# battleswitch_v1.net
KiCad netlist of a schematic drawn in EAGLE
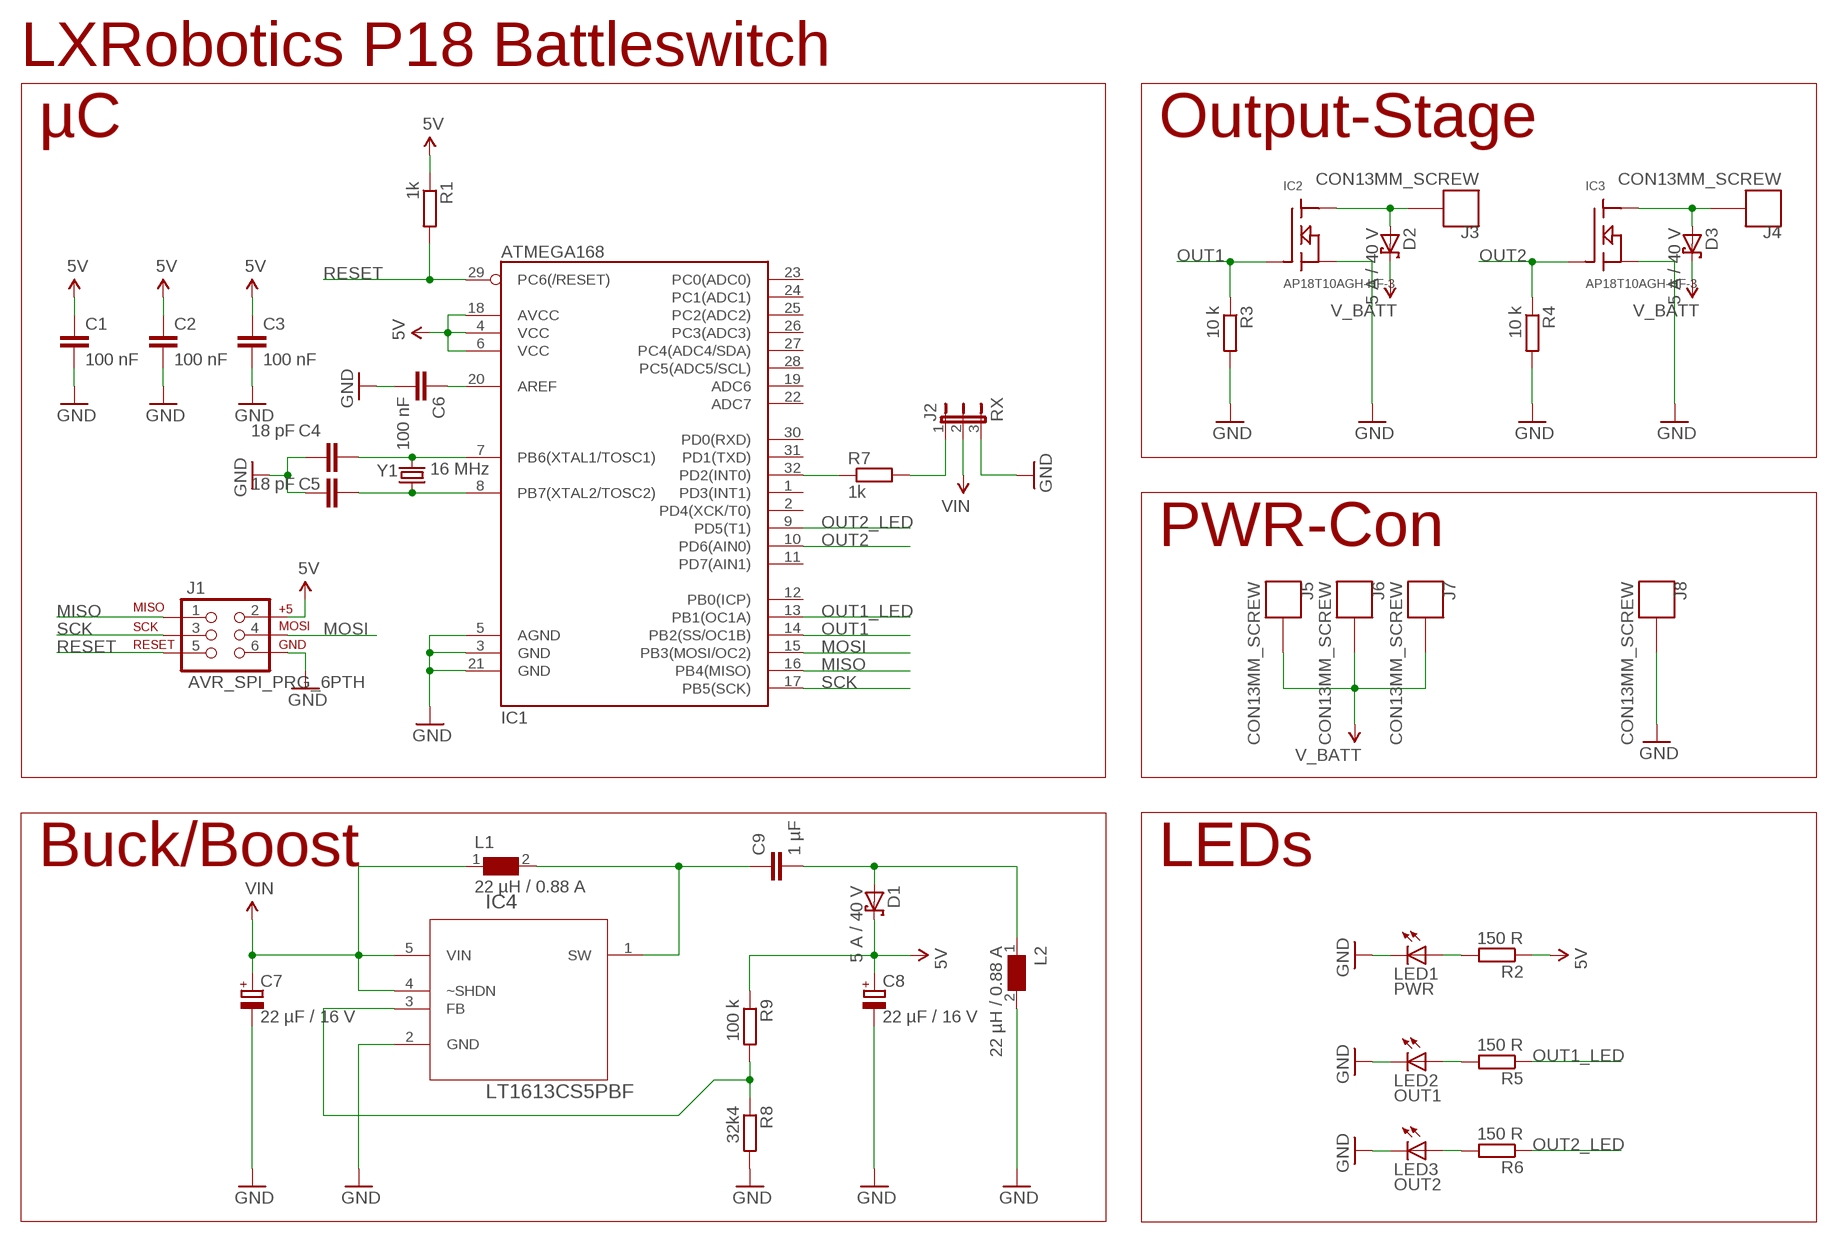
[diagram p0: schematic, sheet 1]

(export (version "E")
  (design (tool "Eeschema 10.0.6"))
  (components
    (comp (ref "C1")
      (value "100 nF")
      (footprint "eagle-import:C0805")
      (libsource (lib "eagle-import") (part "C-EUC0805"))
    )
    (comp (ref "C2")
      (value "100 nF")
      (footprint "eagle-import:C0805")
      (libsource (lib "eagle-import") (part "C-EUC0805"))
    )
    (comp (ref "C3")
      (value "100 nF")
      (footprint "eagle-import:C0805")
      (libsource (lib "eagle-import") (part "C-EUC0805"))
    )
    (comp (ref "C4")
      (value "18 pF")
      (footprint "eagle-import:C0805")
      (libsource (lib "eagle-import") (part "C-EUC0805"))
    )
    (comp (ref "C5")
      (value "18 pF")
      (footprint "eagle-import:C0805")
      (libsource (lib "eagle-import") (part "C-EUC0805"))
    )
    (comp (ref "C6")
      (value "100 nF")
      (footprint "eagle-import:C0805")
      (libsource (lib "eagle-import") (part "C-EUC0805"))
    )
    (comp (ref "C7")
      (value "22 µF / 16 V")
      (footprint "eagle-import:PANASONIC_C")
      (libsource (lib "eagle-import") (part "CPOL-EUC"))
    )
    (comp (ref "C8")
      (value "22 µF / 16 V")
      (footprint "eagle-import:PANASONIC_C")
      (libsource (lib "eagle-import") (part "CPOL-EUC"))
    )
    (comp (ref "C9")
      (value "1 µF")
      (footprint "eagle-import:C0805")
      (libsource (lib "eagle-import") (part "C-EUC0805"))
    )
    (comp (ref "D1")
      (value "5 A / 40 V")
      (footprint "eagle-import:SMC")
      (libsource (lib "eagle-import") (part "SCHOTTKY-DIODESMC"))
    )
    (comp (ref "D2")
      (value "5 A / 40 V")
      (footprint "eagle-import:SMC")
      (libsource (lib "eagle-import") (part "SCHOTTKY-DIODESMC"))
    )
    (comp (ref "D3")
      (value "5 A / 40 V")
      (footprint "eagle-import:SMC")
      (libsource (lib "eagle-import") (part "SCHOTTKY-DIODESMC"))
    )
    (comp (ref "IC1")
      (value "ATMEGA168")
      (footprint "eagle-import:TQFP32-08")
      (libsource (lib "eagle-import") (part "ATMEGA168"))
    )
    (comp (ref "IC2")
      (value "AP18T10AGH-HF-3")
      (footprint "eagle-import:TO252")
      (libsource (lib "eagle-import") (part "AP18T10AGH-HF-3"))
    )
    (comp (ref "IC3")
      (value "AP18T10AGH-HF-3")
      (footprint "eagle-import:TO252")
      (libsource (lib "eagle-import") (part "AP18T10AGH-HF-3"))
    )
    (comp (ref "IC4")
      (value "LT1613CS5PBF")
      (footprint "eagle-import:SOT95P280X145-5N")
      (fields (field (name "MPN") "LT1613CS5#PBF"))
      (libsource (lib "eagle-import") (part "LT1613CS5PBF"))
    )
    (comp (ref "J1")
      (value "AVR_SPI_PRG_6PTH")
      (footprint "eagle-import:2X3")
      (libsource (lib "eagle-import") (part "AVR_SPI_PRG_6PTH"))
    )
    (comp (ref "J2")
      (value "RX")
      (footprint "eagle-import:JP2")
      (libsource (lib "eagle-import") (part "JP2E"))
    )
    (comp (ref "J3")
      (value "CON13MM_SCREW")
      (footprint "eagle-import:CON1_3MM_SCREW")
      (libsource (lib "eagle-import") (part "CON13MM_SCREW"))
    )
    (comp (ref "J4")
      (value "CON13MM_SCREW")
      (footprint "eagle-import:CON1_3MM_SCREW")
      (libsource (lib "eagle-import") (part "CON13MM_SCREW"))
    )
    (comp (ref "J5")
      (value "CON13MM_SCREW")
      (footprint "eagle-import:CON1_3MM_SCREW")
      (libsource (lib "eagle-import") (part "CON13MM_SCREW"))
    )
    (comp (ref "J6")
      (value "CON13MM_SCREW")
      (footprint "eagle-import:CON1_3MM_SCREW")
      (libsource (lib "eagle-import") (part "CON13MM_SCREW"))
    )
    (comp (ref "J7")
      (value "CON13MM_SCREW")
      (footprint "eagle-import:CON1_3MM_SCREW")
      (libsource (lib "eagle-import") (part "CON13MM_SCREW"))
    )
    (comp (ref "J8")
      (value "CON13MM_SCREW")
      (footprint "eagle-import:CON1_3MM_SCREW")
      (libsource (lib "eagle-import") (part "CON13MM_SCREW"))
    )
    (comp (ref "L1")
      (value "22 µH / 0.88 A")
      (footprint "eagle-import:WE-TPC_4818_4828")
      (fields (field (name "MPN") "744042220 "))
      (libsource (lib "eagle-import") (part "WE-TPC_4818/4828-744042220"))
    )
    (comp (ref "L2")
      (value "22 µH / 0.88 A")
      (footprint "eagle-import:WE-TPC_4818_4828")
      (fields (field (name "MPN") "744042220 "))
      (libsource (lib "eagle-import") (part "WE-TPC_4818/4828-744042220"))
    )
    (comp (ref "LED1")
      (value "PWR")
      (footprint "eagle-import:CHIP-LED0805")
      (libsource (lib "eagle-import") (part "LEDCHIP-LED0805"))
    )
    (comp (ref "LED2")
      (value "OUT1")
      (footprint "eagle-import:CHIP-LED0805")
      (libsource (lib "eagle-import") (part "LEDCHIP-LED0805"))
    )
    (comp (ref "LED3")
      (value "OUT2")
      (footprint "eagle-import:CHIP-LED0805")
      (libsource (lib "eagle-import") (part "LEDCHIP-LED0805"))
    )
    (comp (ref "R1")
      (value "1k")
      (footprint "eagle-import:R0805")
      (libsource (lib "eagle-import") (part "R-EU_R0805"))
    )
    (comp (ref "R2")
      (value "150 R")
      (footprint "eagle-import:R0805")
      (libsource (lib "eagle-import") (part "R-EU_R0805"))
    )
    (comp (ref "R3")
      (value "10 k")
      (footprint "eagle-import:R0805")
      (libsource (lib "eagle-import") (part "R-EU_R0805"))
    )
    (comp (ref "R4")
      (value "10 k")
      (footprint "eagle-import:R0805")
      (libsource (lib "eagle-import") (part "R-EU_R0805"))
    )
    (comp (ref "R5")
      (value "150 R")
      (footprint "eagle-import:R0805")
      (libsource (lib "eagle-import") (part "R-EU_R0805"))
    )
    (comp (ref "R6")
      (value "150 R")
      (footprint "eagle-import:R0805")
      (libsource (lib "eagle-import") (part "R-EU_R0805"))
    )
    (comp (ref "R7")
      (value "1k")
      (footprint "eagle-import:R0805")
      (libsource (lib "eagle-import") (part "R-EU_R0805"))
    )
    (comp (ref "R8")
      (value "32k4")
      (footprint "eagle-import:R0805")
      (libsource (lib "eagle-import") (part "R-EU_R0805"))
    )
    (comp (ref "R9")
      (value "100 k")
      (footprint "eagle-import:R0805")
      (libsource (lib "eagle-import") (part "R-EU_R0805"))
    )
    (comp (ref "Y1")
      (value "16 MHz")
      (footprint "eagle-import:HC49US")
      (libsource (lib "eagle-import") (part "CRYSTALHC49US"))
    )
  )
  (nets
    (net (code "1") (name "/MISO") (class "Default")
      (node (ref "IC1") (pin "16") (pinfunction "PB4(MISO)_16") (pintype "bidirectional"))
      (node (ref "J1") (pin "1") (pinfunction "1_1") (pintype "passive"))
    )
    (net (code "2") (name "/MOSI") (class "Default")
      (node (ref "IC1") (pin "15") (pinfunction "PB3(MOSI/OC2)_15") (pintype "bidirectional"))
      (node (ref "J1") (pin "4") (pinfunction "4_4") (pintype "passive"))
    )
    (net (code "3") (name "/OUT1") (class "Default")
      (node (ref "IC1") (pin "14") (pinfunction "PB2(SS/OC1B)_14") (pintype "bidirectional"))
      (node (ref "IC2") (pin "G") (pinfunction "G_G") (pintype "bidirectional"))
      (node (ref "R3") (pin "1") (pinfunction "1_1") (pintype "passive"))
    )
    (net (code "4") (name "/OUT1_LED") (class "Default")
      (node (ref "IC1") (pin "13") (pinfunction "PB1(OC1A)_13") (pintype "bidirectional"))
      (node (ref "R5") (pin "1") (pinfunction "1_1") (pintype "passive"))
    )
    (net (code "5") (name "/OUT2") (class "Default")
      (node (ref "IC1") (pin "10") (pinfunction "PD6(AIN0)_10") (pintype "bidirectional"))
      (node (ref "IC3") (pin "G") (pinfunction "G_G") (pintype "bidirectional"))
      (node (ref "R4") (pin "1") (pinfunction "1_1") (pintype "passive"))
    )
    (net (code "6") (name "/OUT2_LED") (class "Default")
      (node (ref "IC1") (pin "9") (pinfunction "PD5(T1)_9") (pintype "bidirectional"))
      (node (ref "R6") (pin "1") (pinfunction "1_1") (pintype "passive"))
    )
    (net (code "7") (name "/RESET") (class "Default")
      (node (ref "IC1") (pin "29") (pinfunction "PC6(/RESET)_29") (pintype "bidirectional"))
      (node (ref "J1") (pin "5") (pinfunction "5_5") (pintype "passive"))
      (node (ref "R1") (pin "2") (pinfunction "2_2") (pintype "passive"))
    )
    (net (code "8") (name "/SCK") (class "Default")
      (node (ref "IC1") (pin "17") (pinfunction "PB5(SCK)_17") (pintype "bidirectional"))
      (node (ref "J1") (pin "3") (pinfunction "3_3") (pintype "passive"))
    )
    (net (code "9") (name "5V") (class "Default")
      (node (ref "C1") (pin "1") (pinfunction "1_1") (pintype "passive"))
      (node (ref "C2") (pin "1") (pinfunction "1_1") (pintype "passive"))
      (node (ref "C3") (pin "1") (pinfunction "1_1") (pintype "passive"))
      (node (ref "C8") (pin "+") (pinfunction "+_+") (pintype "passive"))
      (node (ref "D1") (pin "C") (pinfunction "C_C") (pintype "passive"))
      (node (ref "IC1") (pin "18") (pinfunction "AVCC_18") (pintype "bidirectional"))
      (node (ref "IC1") (pin "4") (pinfunction "VCC_4") (pintype "bidirectional"))
      (node (ref "IC1") (pin "6") (pinfunction "VCC_6") (pintype "bidirectional"))
      (node (ref "J1") (pin "2") (pinfunction "2_2") (pintype "passive"))
      (node (ref "R1") (pin "1") (pinfunction "1_1") (pintype "passive"))
      (node (ref "R2") (pin "1") (pinfunction "1_1") (pintype "passive"))
      (node (ref "R9") (pin "1") (pinfunction "1_1") (pintype "passive"))
    )
    (net (code "10") (name "GND") (class "Default")
      (node (ref "C1") (pin "2") (pinfunction "2_2") (pintype "passive"))
      (node (ref "C2") (pin "2") (pinfunction "2_2") (pintype "passive"))
      (node (ref "C3") (pin "2") (pinfunction "2_2") (pintype "passive"))
      (node (ref "C4") (pin "2") (pinfunction "2_2") (pintype "passive"))
      (node (ref "C5") (pin "2") (pinfunction "2_2") (pintype "passive"))
      (node (ref "C6") (pin "2") (pinfunction "2_2") (pintype "passive"))
      (node (ref "C7") (pin "-") (pinfunction "-_-") (pintype "passive"))
      (node (ref "C8") (pin "-") (pinfunction "-_-") (pintype "passive"))
      (node (ref "IC1") (pin "21") (pinfunction "GND_21") (pintype "bidirectional"))
      (node (ref "IC1") (pin "3") (pinfunction "GND_3") (pintype "bidirectional"))
      (node (ref "IC1") (pin "5") (pinfunction "AGND_5") (pintype "bidirectional"))
      (node (ref "IC2") (pin "S") (pinfunction "S_S") (pintype "bidirectional"))
      (node (ref "IC3") (pin "S") (pinfunction "S_S") (pintype "bidirectional"))
      (node (ref "IC4") (pin "2") (pinfunction "GND_2") (pintype "passive"))
      (node (ref "J1") (pin "6") (pinfunction "6_6") (pintype "passive"))
      (node (ref "J2") (pin "3") (pinfunction "3_3") (pintype "passive"))
      (node (ref "J8") (pin "P$1") (pinfunction "P$1_P$1") (pintype "bidirectional"))
      (node (ref "L2") (pin "2") (pinfunction "2_2") (pintype "passive"))
      (node (ref "LED1") (pin "C") (pinfunction "C_C") (pintype "passive"))
      (node (ref "LED2") (pin "C") (pinfunction "C_C") (pintype "passive"))
      (node (ref "LED3") (pin "C") (pinfunction "C_C") (pintype "passive"))
      (node (ref "R3") (pin "2") (pinfunction "2_2") (pintype "passive"))
      (node (ref "R4") (pin "2") (pinfunction "2_2") (pintype "passive"))
      (node (ref "R8") (pin "2") (pinfunction "2_2") (pintype "passive"))
    )
    (net (code "11") (name "Net-(C9-Pad2)") (class "Default")
      (node (ref "C9") (pin "2") (pinfunction "2_2") (pintype "passive"))
      (node (ref "D1") (pin "A") (pinfunction "A_A") (pintype "passive"))
      (node (ref "L2") (pin "1") (pinfunction "1_1") (pintype "passive"))
    )
    (net (code "12") (name "Net-(D2-PadA)") (class "Default")
      (node (ref "D2") (pin "A") (pinfunction "A_A") (pintype "passive"))
      (node (ref "IC2") (pin "D") (pinfunction "D_D") (pintype "bidirectional"))
      (node (ref "J3") (pin "P$1") (pinfunction "P$1_P$1") (pintype "bidirectional"))
    )
    (net (code "13") (name "Net-(D3-PadA)") (class "Default")
      (node (ref "D3") (pin "A") (pinfunction "A_A") (pintype "passive"))
      (node (ref "IC3") (pin "D") (pinfunction "D_D") (pintype "bidirectional"))
      (node (ref "J4") (pin "P$1") (pinfunction "P$1_P$1") (pintype "bidirectional"))
    )
    (net (code "14") (name "Net-(IC1-AREF)") (class "Default")
      (node (ref "C6") (pin "1") (pinfunction "1_1") (pintype "passive"))
      (node (ref "IC1") (pin "20") (pinfunction "AREF_20") (pintype "bidirectional"))
    )
    (net (code "15") (name "Net-(IC1-PB6(XTAL1{slash}TOSC1))") (class "Default")
      (node (ref "C4") (pin "1") (pinfunction "1_1") (pintype "passive"))
      (node (ref "IC1") (pin "7") (pinfunction "PB6(XTAL1/TOSC1)_7") (pintype "bidirectional"))
      (node (ref "Y1") (pin "2") (pinfunction "2_2") (pintype "passive"))
    )
    (net (code "16") (name "Net-(IC1-PB7(XTAL2{slash}TOSC2))") (class "Default")
      (node (ref "C5") (pin "1") (pinfunction "1_1") (pintype "passive"))
      (node (ref "IC1") (pin "8") (pinfunction "PB7(XTAL2/TOSC2)_8") (pintype "bidirectional"))
      (node (ref "Y1") (pin "1") (pinfunction "1_1") (pintype "passive"))
    )
    (net (code "17") (name "Net-(IC1-PD2(INT0))") (class "Default")
      (node (ref "IC1") (pin "32") (pinfunction "PD2(INT0)_32") (pintype "bidirectional"))
      (node (ref "R7") (pin "1") (pinfunction "1_1") (pintype "passive"))
    )
    (net (code "18") (name "Net-(IC4-FB)") (class "Default")
      (node (ref "IC4") (pin "3") (pinfunction "FB_3") (pintype "input"))
      (node (ref "R8") (pin "1") (pinfunction "1_1") (pintype "passive"))
      (node (ref "R9") (pin "2") (pinfunction "2_2") (pintype "passive"))
    )
    (net (code "19") (name "Net-(IC4-SW)") (class "Default")
      (node (ref "C9") (pin "1") (pinfunction "1_1") (pintype "passive"))
      (node (ref "IC4") (pin "1") (pinfunction "SW_1") (pintype "output"))
      (node (ref "L1") (pin "2") (pinfunction "2_2") (pintype "passive"))
    )
    (net (code "20") (name "Net-(J2-Pad1)") (class "Default")
      (node (ref "J2") (pin "1") (pinfunction "1_1") (pintype "passive"))
      (node (ref "R7") (pin "2") (pinfunction "2_2") (pintype "passive"))
    )
    (net (code "21") (name "Net-(LED1-PadA)") (class "Default")
      (node (ref "LED1") (pin "A") (pinfunction "A_A") (pintype "passive"))
      (node (ref "R2") (pin "2") (pinfunction "2_2") (pintype "passive"))
    )
    (net (code "22") (name "Net-(LED2-PadA)") (class "Default")
      (node (ref "LED2") (pin "A") (pinfunction "A_A") (pintype "passive"))
      (node (ref "R5") (pin "2") (pinfunction "2_2") (pintype "passive"))
    )
    (net (code "23") (name "Net-(LED3-PadA)") (class "Default")
      (node (ref "LED3") (pin "A") (pinfunction "A_A") (pintype "passive"))
      (node (ref "R6") (pin "2") (pinfunction "2_2") (pintype "passive"))
    )
    (net (code "24") (name "VIN") (class "Default")
      (node (ref "C7") (pin "+") (pinfunction "+_+") (pintype "passive"))
      (node (ref "IC4") (pin "4") (pinfunction "~{SHDN}_4") (pintype "input"))
      (node (ref "IC4") (pin "5") (pinfunction "VIN_5") (pintype "power_in"))
      (node (ref "J2") (pin "2") (pinfunction "2_2") (pintype "passive"))
      (node (ref "L1") (pin "1") (pinfunction "1_1") (pintype "passive"))
    )
    (net (code "25") (name "V_BATT") (class "Default")
      (node (ref "D2") (pin "C") (pinfunction "C_C") (pintype "passive"))
      (node (ref "D3") (pin "C") (pinfunction "C_C") (pintype "passive"))
      (node (ref "J5") (pin "P$1") (pinfunction "P$1_P$1") (pintype "bidirectional"))
      (node (ref "J6") (pin "P$1") (pinfunction "P$1_P$1") (pintype "bidirectional"))
      (node (ref "J7") (pin "P$1") (pinfunction "P$1_P$1") (pintype "bidirectional"))
    )
    (net (code "26") (name "unconnected-(IC1-ADC6-Pad19)") (class "Default")
      (node (ref "IC1") (pin "19") (pinfunction "ADC6_19") (pintype "bidirectional"))
    )
    (net (code "27") (name "unconnected-(IC1-ADC7-Pad22)") (class "Default")
      (node (ref "IC1") (pin "22") (pinfunction "ADC7_22") (pintype "bidirectional"))
    )
    (net (code "28") (name "unconnected-(IC1-PB0(ICP)-Pad12)") (class "Default")
      (node (ref "IC1") (pin "12") (pinfunction "PB0(ICP)_12") (pintype "bidirectional"))
    )
    (net (code "29") (name "unconnected-(IC1-PC0(ADC0)-Pad23)") (class "Default")
      (node (ref "IC1") (pin "23") (pinfunction "PC0(ADC0)_23") (pintype "bidirectional"))
    )
    (net (code "30") (name "unconnected-(IC1-PC1(ADC1)-Pad24)") (class "Default")
      (node (ref "IC1") (pin "24") (pinfunction "PC1(ADC1)_24") (pintype "bidirectional"))
    )
    (net (code "31") (name "unconnected-(IC1-PC2(ADC2)-Pad25)") (class "Default")
      (node (ref "IC1") (pin "25") (pinfunction "PC2(ADC2)_25") (pintype "bidirectional"))
    )
    (net (code "32") (name "unconnected-(IC1-PC3(ADC3)-Pad26)") (class "Default")
      (node (ref "IC1") (pin "26") (pinfunction "PC3(ADC3)_26") (pintype "bidirectional"))
    )
    (net (code "33") (name "unconnected-(IC1-PC4(ADC4{slash}SDA)-Pad27)") (class "Default")
      (node (ref "IC1") (pin "27") (pinfunction "PC4(ADC4/SDA)_27") (pintype "bidirectional"))
    )
    (net (code "34") (name "unconnected-(IC1-PC5(ADC5{slash}SCL)-Pad28)") (class "Default")
      (node (ref "IC1") (pin "28") (pinfunction "PC5(ADC5/SCL)_28") (pintype "bidirectional"))
    )
    (net (code "35") (name "unconnected-(IC1-PD0(RXD)-Pad30)") (class "Default")
      (node (ref "IC1") (pin "30") (pinfunction "PD0(RXD)_30") (pintype "bidirectional"))
    )
    (net (code "36") (name "unconnected-(IC1-PD1(TXD)-Pad31)") (class "Default")
      (node (ref "IC1") (pin "31") (pinfunction "PD1(TXD)_31") (pintype "bidirectional"))
    )
    (net (code "37") (name "unconnected-(IC1-PD3(INT1)-Pad1)") (class "Default")
      (node (ref "IC1") (pin "1") (pinfunction "PD3(INT1)_1") (pintype "bidirectional"))
    )
    (net (code "38") (name "unconnected-(IC1-PD4(XCK{slash}T0)-Pad2)") (class "Default")
      (node (ref "IC1") (pin "2") (pinfunction "PD4(XCK/T0)_2") (pintype "bidirectional"))
    )
    (net (code "39") (name "unconnected-(IC1-PD7(AIN1)-Pad11)") (class "Default")
      (node (ref "IC1") (pin "11") (pinfunction "PD7(AIN1)_11") (pintype "bidirectional"))
    )
  )
)
